# Emergency_Thermal_Shutdown.net
KiCad netlist of a schematic drawn in Altium Designer
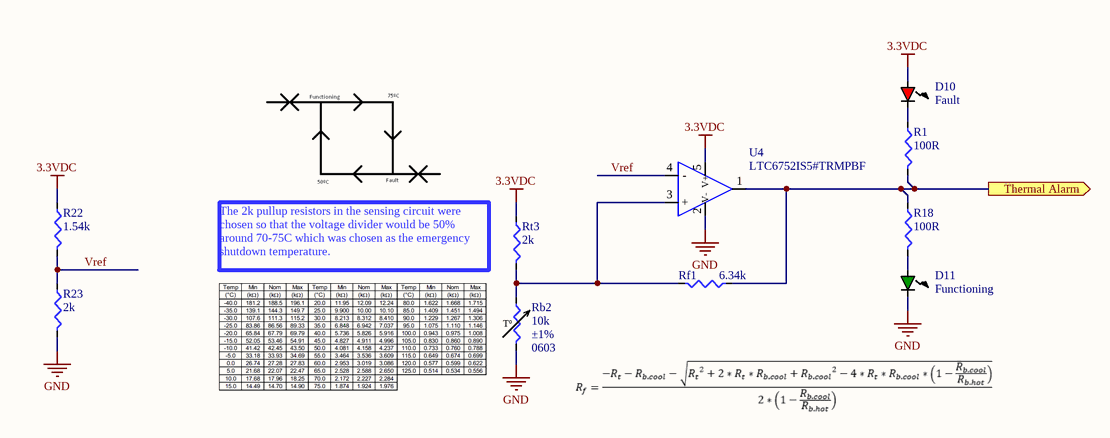
[diagram p0: Emergency Thermal Shutdown.SchDoc]

(export (version "E")
  (design (tool "Eeschema 10.0.6"))
  (components
    (comp (ref "D10")
      (value "Fault")
      (footprint "LED - 1206 Red")
      (fields
        (field (name "MANUFACTURER") "Kingbright")
        (field (name "MANUFACTURER PART NUMBER") "APT3216SRCPRV")
      )
      (libsource (lib "Personal Library") (part "Red LED 1206"))
    )
    (comp (ref "D11")
      (value "Functioning")
      (footprint "LED - 1206 Green")
      (fields
        (field (name "MANUFACTURER") "Kingbright")
        (field (name "MANUFACTURER PART NUMBER") "APL3015SGC-F01")
      )
      (libsource (lib "Personal Library") (part "Green LED 1206"))
    )
    (comp (ref "R1")
      (value "100R 0603 1%")
      (footprint "R0603")
      (description "1/8W")
      (fields
        (field (name "MANUFACTURER") "Yageo")
        (field (name "MANUFACTURER PART NUMBER") "RC0603FR-07100RL")
        (field (name "RESISTANCE (OHMS)") "100R")
      )
      (libsource (lib "Personal Library") (part "100R 0603 1%"))
    )
    (comp (ref "R18")
      (value "100R 0603 1%")
      (footprint "R0603")
      (description "1/8W")
      (fields
        (field (name "MANUFACTURER") "Yageo")
        (field (name "MANUFACTURER PART NUMBER") "RC0603FR-07100RL")
        (field (name "RESISTANCE (OHMS)") "100R")
      )
      (libsource (lib "Personal Library") (part "100R 0603 1%"))
    )
    (comp (ref "R22")
      (value "1.54k 0603 1%")
      (footprint "R0603")
      (fields
        (field (name "MANUFACTURER") "Yageo")
        (field (name "MANUFACTURER PART NUMBER") "RC0603FR-071K54L")
        (field (name "TOLERANCE") "±1%")
        (field (name "RESISTANCE") "1.54k")
      )
      (libsource (lib "Local Library") (part "1.54k 0603 1%"))
    )
    (comp (ref "R23")
      (value "2k 0603 1%")
      (footprint "R0603")
      (fields
        (field (name "MANUFACTURER") "Panasonic Electronic Components")
        (field (name "MANUFACTURER PART NUMBER") "ERJ-3EKF2001V")
        (field (name "TOLERANCE") "±1%")
        (field (name "RESISTANCE (OHMS)") "2k")
      )
      (libsource (lib "Personal Library") (part "2k 0603 1%"))
    )
    (comp (ref "Rb2")
      (value "Thermistor 10k Type J SMT")
      (description "Resistor")
      (fields
        (field (name "MANUFACTURER") "TDK Corporation")
        (field (name "MANUFACTURER PART NUMBER") "NTCG163JF103FTDS")
        (field (name "RESISTANCE IN OHMS @ 25°C") "10k")
        (field (name "RESISTANCE TOLERANCE") "±1%")
        (field (name "PACKAGE / CASE") "0603")
      )
      (libsource (lib "Local Library") (part "Thermistor 10k Type J SMT"))
    )
    (comp (ref "Rf1")
      (value "6.34k 0603 1%")
      (footprint "R0603")
      (fields
        (field (name "MANUFACTURER") "Yageo")
        (field (name "MANUFACTURER PART NUMBER") "RC0603FR-076K34L")
        (field (name "TOLERANCE") "±1%")
        (field (name "RESISTANCE") "6.34k")
      )
      (libsource (lib "Local Library") (part "6.34k 0603 1%"))
    )
    (comp (ref "Rt3")
      (value "2k 0603 1%")
      (footprint "R0603")
      (fields
        (field (name "MANUFACTURER") "Panasonic Electronic Components")
        (field (name "MANUFACTURER PART NUMBER") "ERJ-3EKF2001V")
        (field (name "TOLERANCE") "±1%")
        (field (name "RESISTANCE (OHMS)") "2k")
      )
      (libsource (lib "Personal Library") (part "2k 0603 1%"))
    )
    (comp (ref "U4")
      (value "Single Comparator LTC6752")
      (fields
        (field (name "MANUFACTURER") "Linear Technology")
        (field (name "MANUFACTURER PART NUMBER") "LTC6752IS5#TRMPBF")
      )
      (libsource (lib "Local Library") (part "Single Comparator LTC6752"))
    )
  )
  (nets
    (net (code "1") (name "/Thermal Alarm") (class "Default")
      (node (ref "R1") (pin "1") (pinfunction "1_1") (pintype "passive"))
      (node (ref "R18") (pin "2") (pinfunction "2_2") (pintype "passive"))
      (node (ref "Rf1") (pin "2") (pinfunction "2_2") (pintype "passive"))
      (node (ref "U4") (pin "1") (pinfunction "Out_1") (pintype "passive"))
    )
    (net (code "2") (name "/Vref") (class "Default")
      (node (ref "R22") (pin "1") (pinfunction "1_1") (pintype "passive"))
      (node (ref "R23") (pin "2") (pinfunction "2_2") (pintype "passive"))
      (node (ref "U4") (pin "4") (pinfunction "-_4") (pintype "passive"))
    )
    (net (code "3") (name "3.3VDC") (class "Default")
      (node (ref "D10") (pin "1") (pinfunction "1_1") (pintype "passive"))
      (node (ref "R22") (pin "2") (pinfunction "2_2") (pintype "passive"))
      (node (ref "Rt3") (pin "2") (pinfunction "2_2") (pintype "passive"))
      (node (ref "U4") (pin "5") (pinfunction "V+_5") (pintype "passive"))
    )
    (net (code "4") (name "GND") (class "Default")
      (node (ref "D11") (pin "2") (pinfunction "2_2") (pintype "passive"))
      (node (ref "R23") (pin "1") (pinfunction "1_1") (pintype "passive"))
      (node (ref "Rb2") (pin "2") (pinfunction "2_2") (pintype "passive"))
      (node (ref "U4") (pin "2") (pinfunction "V-_2") (pintype "passive"))
    )
    (net (code "5") (name "Net-(D10-Pad2)") (class "Default")
      (node (ref "D10") (pin "2") (pinfunction "2_2") (pintype "passive"))
      (node (ref "R1") (pin "2") (pinfunction "2_2") (pintype "passive"))
    )
    (net (code "6") (name "Net-(D11-Pad1)") (class "Default")
      (node (ref "D11") (pin "1") (pinfunction "1_1") (pintype "passive"))
      (node (ref "R18") (pin "1") (pinfunction "1_1") (pintype "passive"))
    )
    (net (code "7") (name "Net-(U4-+)") (class "Default")
      (node (ref "Rb2") (pin "1") (pinfunction "1_1") (pintype "passive"))
      (node (ref "Rf1") (pin "1") (pinfunction "1_1") (pintype "passive"))
      (node (ref "Rt3") (pin "1") (pinfunction "1_1") (pintype "passive"))
      (node (ref "U4") (pin "3") (pinfunction "+_3") (pintype "passive"))
    )
  )
)
